# DummyLoad.net
KiCad netlist of a schematic drawn in EAGLE
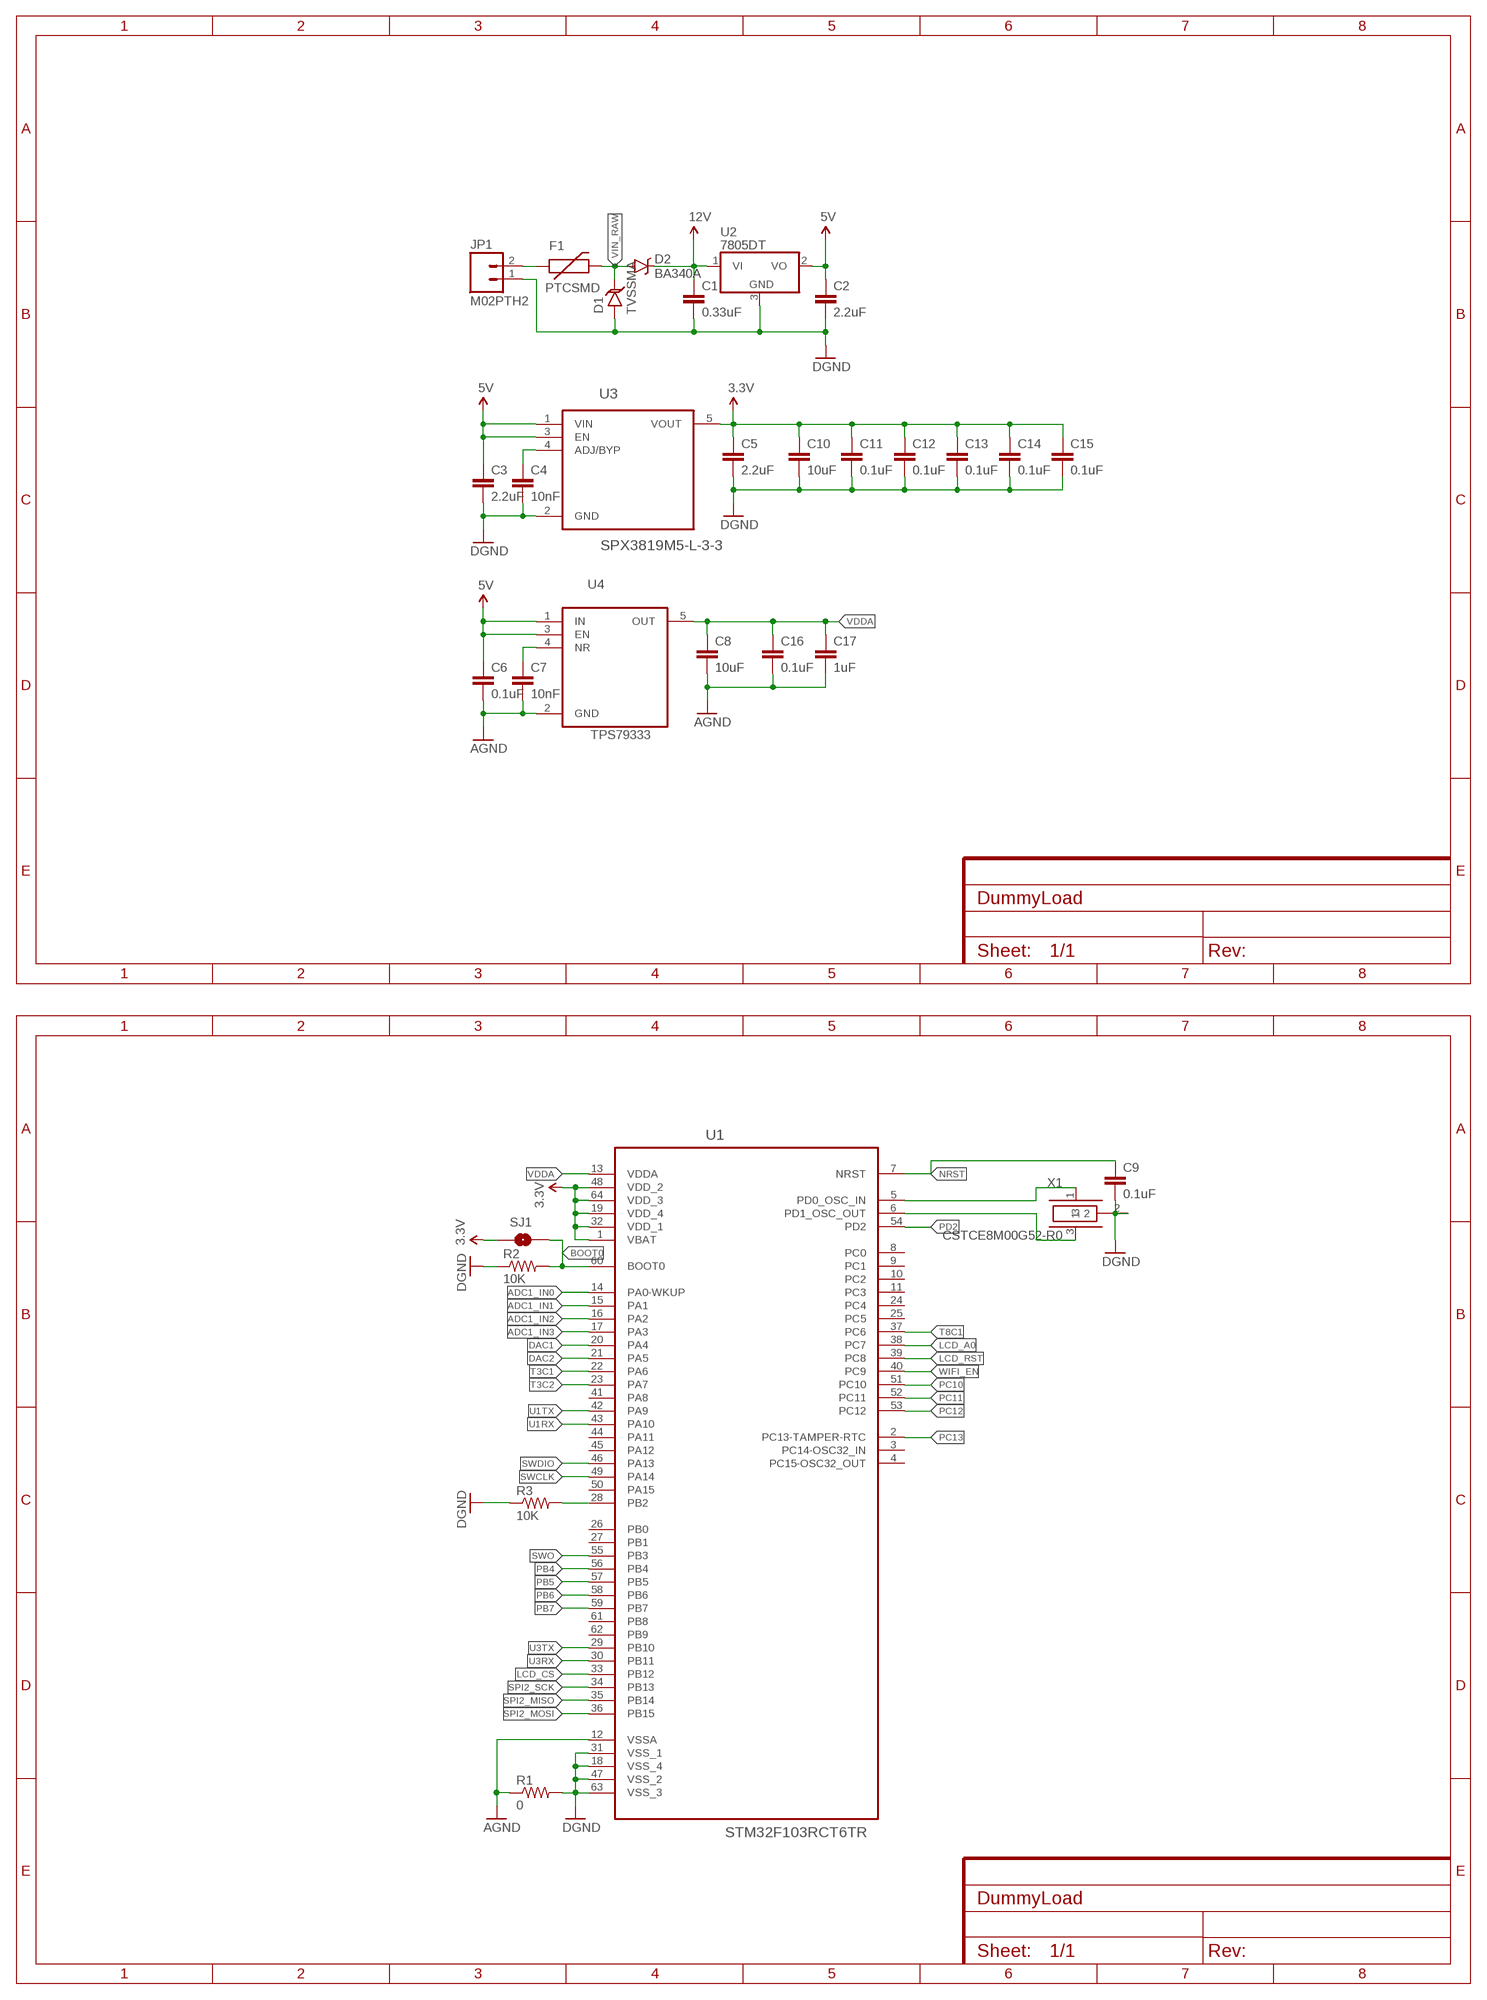
[diagram p0: schematic, sheet 1, part 1 of 2]
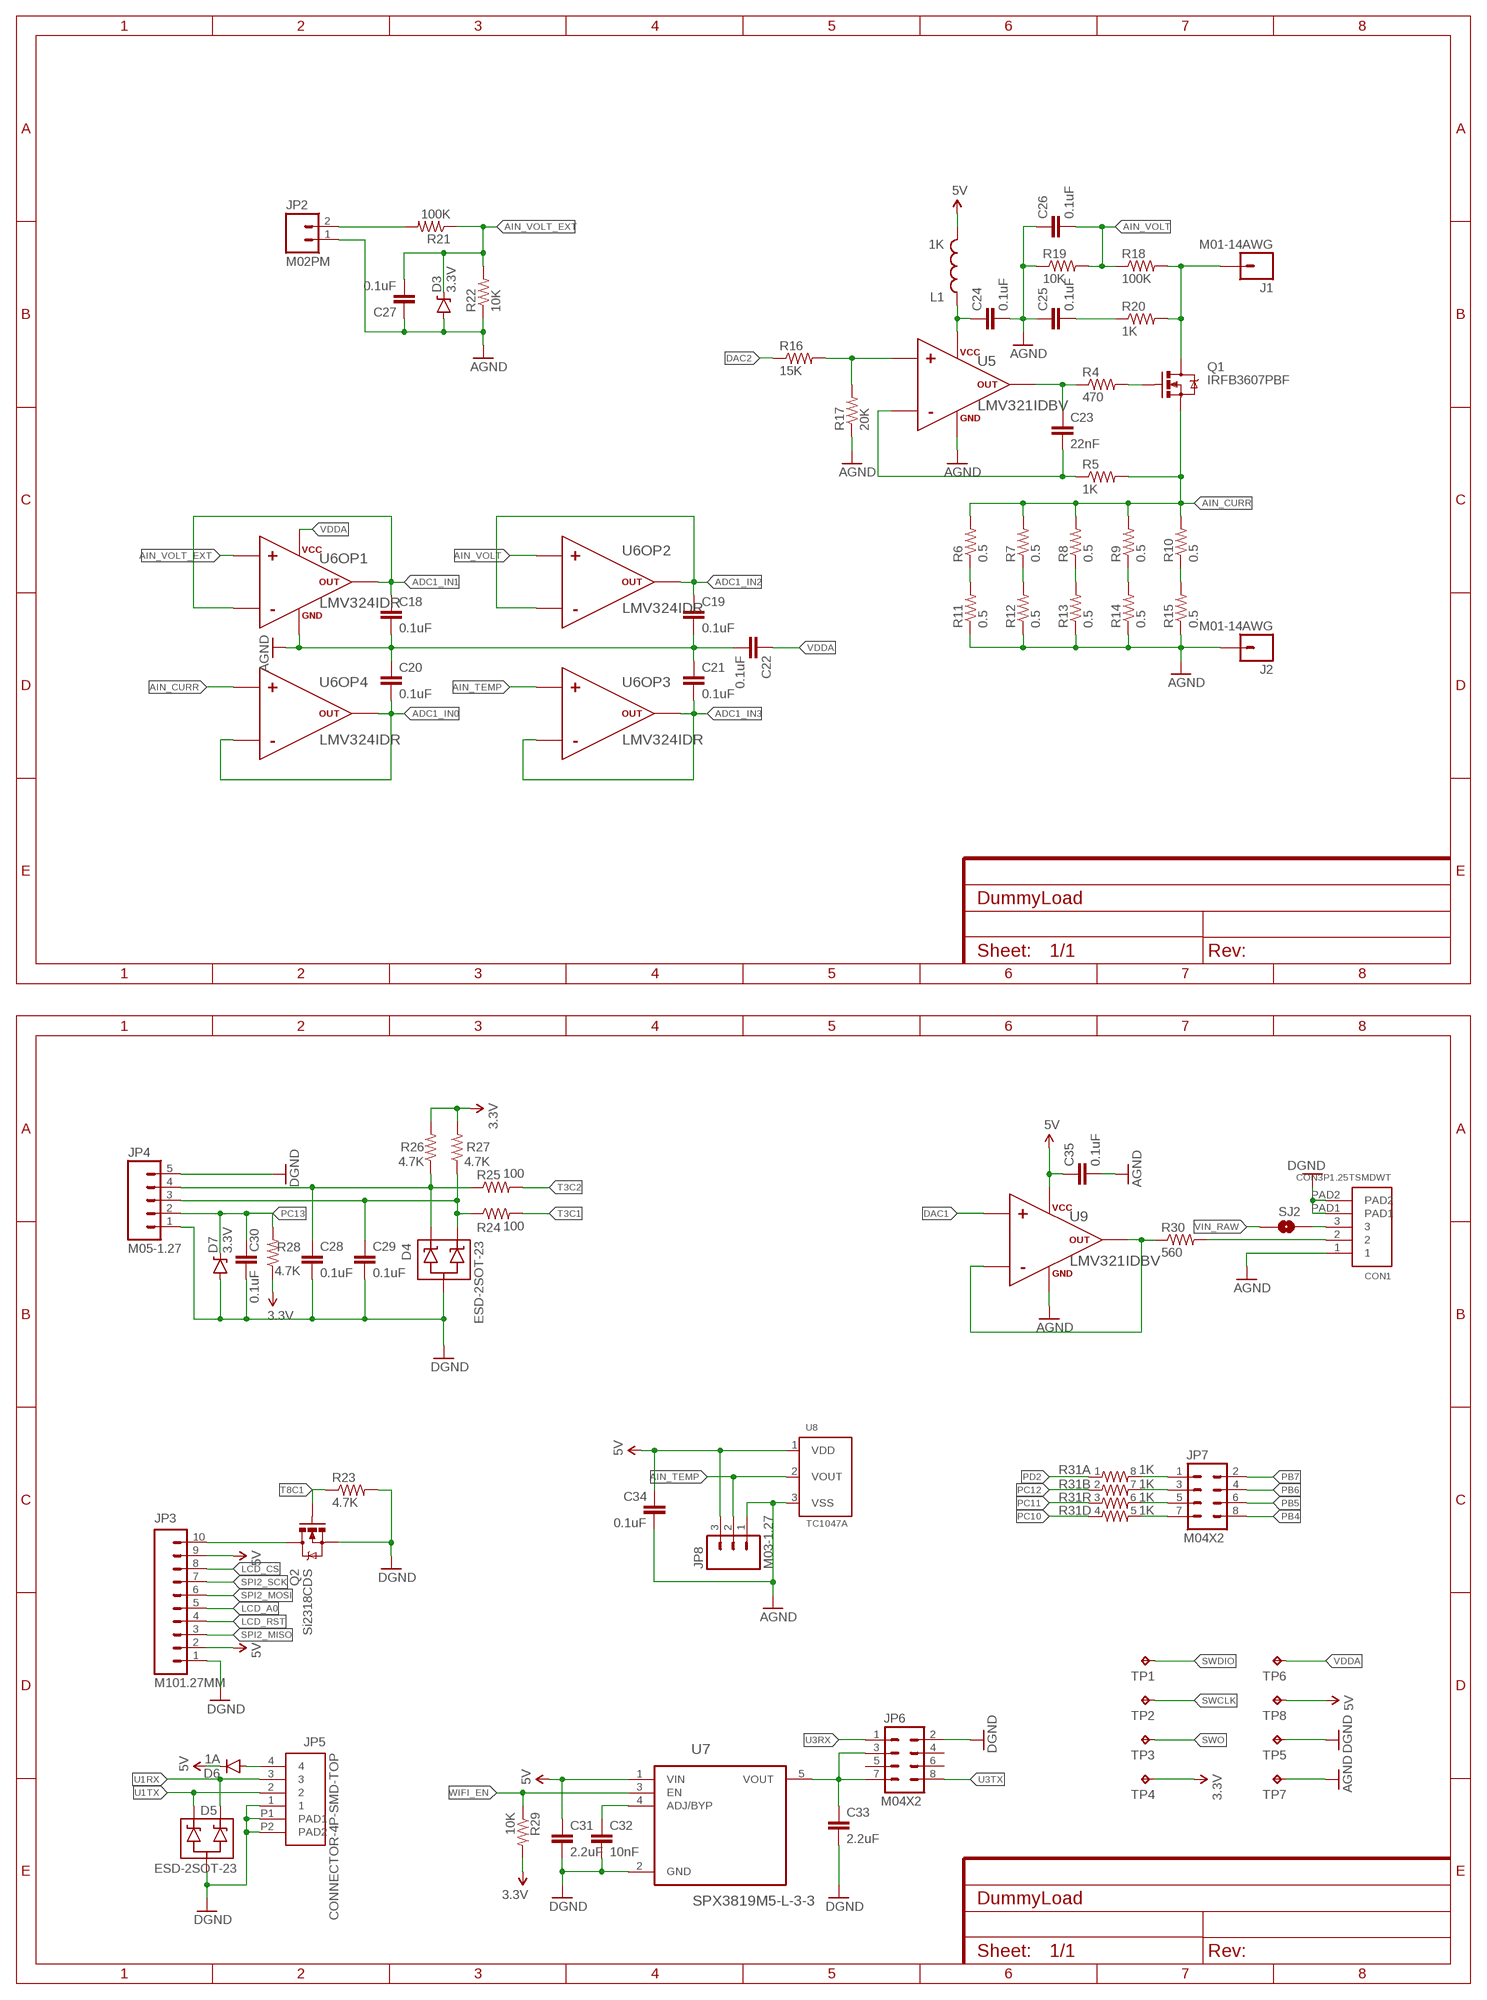
[diagram p1: schematic, sheet 1, part 2 of 2]

(export (version "E")
  (design (tool "Eeschema 10.0.6"))
  (components
    (comp (ref "C1")
      (value "0.33uF")
      (footprint "eagle-import:0603-CAP")
      (libsource (lib "eagle-import") (part "CAP0603-CAP"))
    )
    (comp (ref "C2")
      (value "2.2uF")
      (footprint "eagle-import:0603-CAP")
      (libsource (lib "eagle-import") (part "CAP0603-CAP"))
    )
    (comp (ref "C3")
      (value "2.2uF")
      (footprint "eagle-import:0603-CAP")
      (libsource (lib "eagle-import") (part "CAP0603-CAP"))
    )
    (comp (ref "C4")
      (value "10nF")
      (footprint "eagle-import:0603-CAP")
      (libsource (lib "eagle-import") (part "CAP0603-CAP"))
    )
    (comp (ref "C5")
      (value "2.2uF")
      (footprint "eagle-import:0603-CAP")
      (libsource (lib "eagle-import") (part "CAP0603-CAP"))
    )
    (comp (ref "C6")
      (value "0.1uF")
      (footprint "eagle-import:0603-CAP")
      (libsource (lib "eagle-import") (part "CAP0603-CAP"))
    )
    (comp (ref "C7")
      (value "10nF")
      (footprint "eagle-import:0603-CAP")
      (libsource (lib "eagle-import") (part "CAP0603-CAP"))
    )
    (comp (ref "C8")
      (value "10uF")
      (footprint "eagle-import:0603-CAP")
      (libsource (lib "eagle-import") (part "CAP0603-CAP"))
    )
    (comp (ref "C9")
      (value "0.1uF")
      (footprint "eagle-import:0603-CAP")
      (libsource (lib "eagle-import") (part "CAP0603-CAP"))
    )
    (comp (ref "C10")
      (value "10uF")
      (footprint "eagle-import:0603-CAP")
      (libsource (lib "eagle-import") (part "CAP0603-CAP"))
    )
    (comp (ref "C11")
      (value "0.1uF")
      (footprint "eagle-import:0603-CAP")
      (libsource (lib "eagle-import") (part "CAP0603-CAP"))
    )
    (comp (ref "C12")
      (value "0.1uF")
      (footprint "eagle-import:0603-CAP")
      (libsource (lib "eagle-import") (part "CAP0603-CAP"))
    )
    (comp (ref "C13")
      (value "0.1uF")
      (footprint "eagle-import:0603-CAP")
      (libsource (lib "eagle-import") (part "CAP0603-CAP"))
    )
    (comp (ref "C14")
      (value "0.1uF")
      (footprint "eagle-import:0603-CAP")
      (libsource (lib "eagle-import") (part "CAP0603-CAP"))
    )
    (comp (ref "C15")
      (value "0.1uF")
      (footprint "eagle-import:0603-CAP")
      (libsource (lib "eagle-import") (part "CAP0603-CAP"))
    )
    (comp (ref "C16")
      (value "0.1uF")
      (footprint "eagle-import:0603-CAP")
      (libsource (lib "eagle-import") (part "CAP0603-CAP"))
    )
    (comp (ref "C17")
      (value "1uF")
      (footprint "eagle-import:0603-CAP")
      (libsource (lib "eagle-import") (part "CAP0603-CAP"))
    )
    (comp (ref "C18")
      (value "0.1uF")
      (footprint "eagle-import:0603-CAP")
      (libsource (lib "eagle-import") (part "CAP0603-CAP"))
    )
    (comp (ref "C19")
      (value "0.1uF")
      (footprint "eagle-import:0603-CAP")
      (libsource (lib "eagle-import") (part "CAP0603-CAP"))
    )
    (comp (ref "C20")
      (value "0.1uF")
      (footprint "eagle-import:0603-CAP")
      (libsource (lib "eagle-import") (part "CAP0603-CAP"))
    )
    (comp (ref "C21")
      (value "0.1uF")
      (footprint "eagle-import:0603-CAP")
      (libsource (lib "eagle-import") (part "CAP0603-CAP"))
    )
    (comp (ref "C22")
      (value "0.1uF")
      (footprint "eagle-import:0603-CAP")
      (libsource (lib "eagle-import") (part "CAP0603-CAP"))
    )
    (comp (ref "C23")
      (value "22nF")
      (footprint "eagle-import:0603-CAP")
      (libsource (lib "eagle-import") (part "CAP0603-CAP"))
    )
    (comp (ref "C24")
      (value "0.1uF")
      (footprint "eagle-import:0603-CAP")
      (libsource (lib "eagle-import") (part "CAP0603-CAP"))
    )
    (comp (ref "C25")
      (value "0.1uF")
      (footprint "eagle-import:0603-CAP")
      (libsource (lib "eagle-import") (part "0.1UF-25V-5%(0603)"))
    )
    (comp (ref "C26")
      (value "0.1uF")
      (footprint "eagle-import:0603-CAP")
      (libsource (lib "eagle-import") (part "0.1UF-25V-5%(0603)"))
    )
    (comp (ref "C27")
      (value "0.1uF")
      (footprint "eagle-import:0603-CAP")
      (libsource (lib "eagle-import") (part "0.1UF-25V-5%(0603)"))
    )
    (comp (ref "C28")
      (value "0.1uF")
      (footprint "eagle-import:0603-CAP")
      (libsource (lib "eagle-import") (part "CAP0603-CAP"))
    )
    (comp (ref "C29")
      (value "0.1uF")
      (footprint "eagle-import:0603-CAP")
      (libsource (lib "eagle-import") (part "CAP0603-CAP"))
    )
    (comp (ref "C30")
      (value "0.1uF")
      (footprint "eagle-import:0603-CAP")
      (libsource (lib "eagle-import") (part "CAP0603-CAP"))
    )
    (comp (ref "C31")
      (value "2.2uF")
      (footprint "eagle-import:0603-CAP")
      (libsource (lib "eagle-import") (part "CAP0603-CAP"))
    )
    (comp (ref "C32")
      (value "10nF")
      (footprint "eagle-import:0603-CAP")
      (libsource (lib "eagle-import") (part "CAP0603-CAP"))
    )
    (comp (ref "C33")
      (value "2.2uF")
      (footprint "eagle-import:0603-CAP")
      (libsource (lib "eagle-import") (part "CAP0603-CAP"))
    )
    (comp (ref "C34")
      (value "0.1uF")
      (footprint "eagle-import:0603-CAP")
      (libsource (lib "eagle-import") (part "CAP0603-CAP"))
    )
    (comp (ref "C35")
      (value "0.1uF")
      (footprint "eagle-import:0603-CAP")
      (libsource (lib "eagle-import") (part "CAP0603-CAP"))
    )
    (comp (ref "CON1")
      (value "CON3P1.25TSMDWT")
      (footprint "eagle-import:1.25T3P")
      (libsource (lib "eagle-import") (part "CON3P1.25TSMDWT"))
    )
    (comp (ref "D1")
      (value "TVSSMA")
      (footprint "eagle-import:SMA-DIODE")
      (libsource (lib "eagle-import") (part "TVSSMA"))
    )
    (comp (ref "D2")
      (value "BA340A")
      (footprint "eagle-import:SMA-DIODE")
      (libsource (lib "eagle-import") (part "B340A"))
    )
    (comp (ref "D3")
      (value "3.3V")
      (footprint "eagle-import:SOD-323")
      (libsource (lib "eagle-import") (part "DIODE-ZENER3.3V"))
    )
    (comp (ref "D4")
      (value "ESD-2SOT-23")
      (footprint "eagle-import:SOT23-3")
      (libsource (lib "eagle-import") (part "ESD-2SOT-23"))
    )
    (comp (ref "D5")
      (value "ESD-2SOT-23")
      (footprint "eagle-import:SOT23-3")
      (libsource (lib "eagle-import") (part "ESD-2SOT-23"))
    )
    (comp (ref "D6")
      (value "1A")
      (footprint "eagle-import:SOD-123")
      (libsource (lib "eagle-import") (part "DIODESOD123"))
    )
    (comp (ref "D7")
      (value "3.3V")
      (footprint "eagle-import:SOD-323")
      (libsource (lib "eagle-import") (part "DIODE-ZENER3.3V"))
    )
    (comp (ref "F1")
      (value "PTCSMD")
      (footprint "eagle-import:PTC-1206")
      (libsource (lib "eagle-import") (part "PTCSMD"))
    )
    (comp (ref "J1")
      (value "M01-14AWG")
      (footprint "eagle-import:PTH1.8MM")
      (libsource (lib "eagle-import") (part "M01-14AWG"))
    )
    (comp (ref "J2")
      (value "M01-14AWG")
      (footprint "eagle-import:PTH1.8MM")
      (libsource (lib "eagle-import") (part "M01-14AWG"))
    )
    (comp (ref "JP1")
      (value "M02PTH2")
      (footprint "eagle-import:1X02_BIG")
      (libsource (lib "eagle-import") (part "M02PTH2"))
    )
    (comp (ref "JP2")
      (value "M02PM")
      (footprint "eagle-import:1X02_PM")
      (libsource (lib "eagle-import") (part "M02PM"))
    )
    (comp (ref "JP3")
      (value "M101.27MM")
      (footprint "eagle-import:1X10-1.27MM")
      (libsource (lib "eagle-import") (part "M101.27MM"))
    )
    (comp (ref "JP4")
      (value "M05-1.27")
      (footprint "eagle-import:1X05-1.27MM")
      (libsource (lib "eagle-import") (part "M051.27MM"))
    )
    (comp (ref "JP5")
      (value "CONNECTOR-4P-SMD-TOP")
      (footprint "eagle-import:PH2-4T")
      (libsource (lib "eagle-import") (part "CONNECTOR-4P-SMD-TOP"))
    )
    (comp (ref "JP6")
      (value "M04X2")
      (footprint "eagle-import:2X4")
      (libsource (lib "eagle-import") (part "M04X2"))
    )
    (comp (ref "JP7")
      (value "M04X2")
      (footprint "eagle-import:2X4")
      (libsource (lib "eagle-import") (part "M04X2"))
    )
    (comp (ref "JP8")
      (value "M03-1.27")
      (footprint "eagle-import:1X03-1.27MM")
      (libsource (lib "eagle-import") (part "M03M03-1.27MM"))
    )
    (comp (ref "L1")
      (value "1K")
      (footprint "eagle-import:0603")
      (libsource (lib "eagle-import") (part "INDUCTOR0603"))
    )
    (comp (ref "Q1")
      (value "IRFB3607PBF")
      (footprint "eagle-import:TO220V")
      (libsource (lib "eagle-import") (part "MOSFET-NCHANNELFQP30N06L"))
    )
    (comp (ref "Q2")
      (value "Si2318CDS")
      (footprint "eagle-import:SOT23-3")
      (libsource (lib "eagle-import") (part "MOSFET-NCHANNELBSS123LT1G"))
    )
    (comp (ref "R1")
      (value "0")
      (footprint "eagle-import:0603")
      (libsource (lib "eagle-import") (part "0OHM-1/10W-5%(0603)"))
    )
    (comp (ref "R2")
      (value "10K")
      (footprint "eagle-import:0603-RES")
      (libsource (lib "eagle-import") (part "SparkFun-Resistors_RESISTOR0603-RES"))
    )
    (comp (ref "R3")
      (value "10K")
      (footprint "eagle-import:0603-RES")
      (libsource (lib "eagle-import") (part "SparkFun-Resistors_RESISTOR0603-RES"))
    )
    (comp (ref "R4")
      (value "470")
      (footprint "eagle-import:0603-RES")
      (libsource (lib "eagle-import") (part "SparkFun-Resistors_RESISTOR0603-RES"))
    )
    (comp (ref "R5")
      (value "1K")
      (footprint "eagle-import:0603-RES")
      (libsource (lib "eagle-import") (part "SparkFun-Resistors_RESISTOR0603-RES"))
    )
    (comp (ref "R6")
      (value "0.5")
      (footprint "eagle-import:R2512")
      (libsource (lib "eagle-import") (part "SparkFun-Resistors_RESISTOR2512"))
    )
    (comp (ref "R7")
      (value "0.5")
      (footprint "eagle-import:R2512")
      (libsource (lib "eagle-import") (part "SparkFun-Resistors_RESISTOR2512"))
    )
    (comp (ref "R8")
      (value "0.5")
      (footprint "eagle-import:R2512")
      (libsource (lib "eagle-import") (part "SparkFun-Resistors_RESISTOR2512"))
    )
    (comp (ref "R9")
      (value "0.5")
      (footprint "eagle-import:R2512")
      (libsource (lib "eagle-import") (part "SparkFun-Resistors_RESISTOR2512"))
    )
    (comp (ref "R10")
      (value "0.5")
      (footprint "eagle-import:R2512")
      (libsource (lib "eagle-import") (part "SparkFun-Resistors_RESISTOR2512"))
    )
    (comp (ref "R11")
      (value "0.5")
      (footprint "eagle-import:R2512")
      (libsource (lib "eagle-import") (part "SparkFun-Resistors_RESISTOR2512"))
    )
    (comp (ref "R12")
      (value "0.5")
      (footprint "eagle-import:R2512")
      (libsource (lib "eagle-import") (part "SparkFun-Resistors_RESISTOR2512"))
    )
    (comp (ref "R13")
      (value "0.5")
      (footprint "eagle-import:R2512")
      (libsource (lib "eagle-import") (part "SparkFun-Resistors_RESISTOR2512"))
    )
    (comp (ref "R14")
      (value "0.5")
      (footprint "eagle-import:R2512")
      (libsource (lib "eagle-import") (part "SparkFun-Resistors_RESISTOR2512"))
    )
    (comp (ref "R15")
      (value "0.5")
      (footprint "eagle-import:R2512")
      (libsource (lib "eagle-import") (part "SparkFun-Resistors_RESISTOR2512"))
    )
    (comp (ref "R16")
      (value "15K")
      (footprint "eagle-import:0603-RES")
      (libsource (lib "eagle-import") (part "SparkFun-Resistors_RESISTOR0603-RES"))
    )
    (comp (ref "R17")
      (value "20K")
      (footprint "eagle-import:0603-RES")
      (libsource (lib "eagle-import") (part "SparkFun-Resistors_RESISTOR0603-RES"))
    )
    (comp (ref "R18")
      (value "100K")
      (footprint "eagle-import:0603-RES")
      (libsource (lib "eagle-import") (part "SparkFun-Resistors_RESISTOR0603-RES"))
    )
    (comp (ref "R19")
      (value "10K")
      (footprint "eagle-import:0603-RES")
      (libsource (lib "eagle-import") (part "SparkFun-Resistors_RESISTOR0603-RES"))
    )
    (comp (ref "R20")
      (value "1K")
      (footprint "eagle-import:0603-RES")
      (libsource (lib "eagle-import") (part "SparkFun-Resistors_RESISTOR0603-RES"))
    )
    (comp (ref "R21")
      (value "100K")
      (footprint "eagle-import:0603-RES")
      (libsource (lib "eagle-import") (part "SparkFun-Resistors_RESISTOR0603-RES"))
    )
    (comp (ref "R22")
      (value "10K")
      (footprint "eagle-import:0603-RES")
      (libsource (lib "eagle-import") (part "SparkFun-Resistors_RESISTOR0603-RES"))
    )
    (comp (ref "R23")
      (value "4.7K")
      (footprint "eagle-import:0603-RES")
      (libsource (lib "eagle-import") (part "SparkFun-Resistors_RESISTOR0603-RES"))
    )
    (comp (ref "R24")
      (value "100")
      (footprint "eagle-import:0603-RES")
      (libsource (lib "eagle-import") (part "SparkFun-Resistors_RESISTOR0603-RES"))
    )
    (comp (ref "R25")
      (value "100")
      (footprint "eagle-import:0603-RES")
      (libsource (lib "eagle-import") (part "SparkFun-Resistors_RESISTOR0603-RES"))
    )
    (comp (ref "R26")
      (value "4.7K")
      (footprint "eagle-import:0603-RES")
      (libsource (lib "eagle-import") (part "SparkFun-Resistors_RESISTOR0603-RES"))
    )
    (comp (ref "R27")
      (value "4.7K")
      (footprint "eagle-import:0603-RES")
      (libsource (lib "eagle-import") (part "SparkFun-Resistors_RESISTOR0603-RES"))
    )
    (comp (ref "R28")
      (value "4.7K")
      (footprint "eagle-import:0603-RES")
      (libsource (lib "eagle-import") (part "SparkFun-Resistors_RESISTOR0603-RES"))
    )
    (comp (ref "R29")
      (value "10K")
      (footprint "eagle-import:0603-RES")
      (libsource (lib "eagle-import") (part "10KOHM-1/10W-1%(0603)0603"))
    )
    (comp (ref "R30")
      (value "560")
      (footprint "eagle-import:0603-RES")
      (libsource (lib "eagle-import") (part "RESISTOR0603-RES"))
    )
    (comp (ref "R31")
      (value "1K")
      (footprint "eagle-import:0603-ARV")
      (libsource (lib "eagle-import") (part "RESISTOR-ARRAY0603-ARV"))
    )
    (comp (ref "SJ1")
      (value "JUMPER-PAD-2-NOYES_SILK")
      (footprint "eagle-import:PAD-JUMPER-2-NO_YES_SILK")
      (libsource (lib "eagle-import") (part "JUMPER-PAD-2-NOYES_SILK"))
    )
    (comp (ref "SJ2")
      (value "JUMPER-PAD-2-NO")
      (footprint "eagle-import:PAD-JUMPER-2-NO_NO_SILK")
      (libsource (lib "eagle-import") (part "JUMPER-PAD-2-NO"))
    )
    (comp (ref "TP1")
      (value "TPB1,27")
      (footprint "eagle-import:B1,27")
      (libsource (lib "eagle-import") (part "TPB1,27"))
    )
    (comp (ref "TP2")
      (value "TPB1,27")
      (footprint "eagle-import:B1,27")
      (libsource (lib "eagle-import") (part "TPB1,27"))
    )
    (comp (ref "TP3")
      (value "TPB1,27")
      (footprint "eagle-import:B1,27")
      (libsource (lib "eagle-import") (part "TPB1,27"))
    )
    (comp (ref "TP4")
      (value "TPB1,27")
      (footprint "eagle-import:B1,27")
      (libsource (lib "eagle-import") (part "TPB1,27"))
    )
    (comp (ref "TP5")
      (value "TPB1,27")
      (footprint "eagle-import:B1,27")
      (libsource (lib "eagle-import") (part "TPB1,27"))
    )
    (comp (ref "TP6")
      (value "TPB1,27")
      (footprint "eagle-import:B1,27")
      (libsource (lib "eagle-import") (part "TPB1,27"))
    )
    (comp (ref "TP7")
      (value "TPB1,27")
      (footprint "eagle-import:B1,27")
      (libsource (lib "eagle-import") (part "TPB1,27"))
    )
    (comp (ref "TP8")
      (value "TPB1,27")
      (footprint "eagle-import:B1,27")
      (libsource (lib "eagle-import") (part "TPB1,27"))
    )
    (comp (ref "U1")
      (value "STM32F103RCT6TR")
      (footprint "eagle-import:QFP50P1200X1200X160-64N")
      (fields (field (name "MPN") "STM32F103RCT6"))
      (libsource (lib "eagle-import") (part "STM32F103RCT6TR"))
    )
    (comp (ref "U2")
      (value "7805DT")
      (footprint "eagle-import:TO252")
      (libsource (lib "eagle-import") (part "78DT05"))
    )
    (comp (ref "U3")
      (value "SPX3819M5-L-3-3")
      (footprint "eagle-import:SOT95P280X145-5N")
      (libsource (lib "eagle-import") (part "SPX3819M5-L-3-3"))
    )
    (comp (ref "U4")
      (value "TPS79333")
      (footprint "eagle-import:SOT95P280X145-5N")
      (fields (field (name "MPN") "TPS79333DBVR"))
      (libsource (lib "eagle-import") (part "TPS79333"))
    )
    (comp (ref "U5")
      (value "LMV321IDBV")
      (footprint "eagle-import:SOT23-5")
      (fields (field (name "MPN") "LMV321IDBVR"))
      (libsource (lib "eagle-import") (part "LMV321IDBV"))
    )
    (comp (ref "U6")
      (value "LMV324IDR")
      (footprint "eagle-import:SOIC14")
      (libsource (lib "eagle-import") (part "LMV324IDR"))
    )
    (comp (ref "U7")
      (value "SPX3819M5-L-3-3")
      (footprint "eagle-import:SOT95P280X145-5N")
      (libsource (lib "eagle-import") (part "SPX3819M5-L-3-3"))
    )
    (comp (ref "U8")
      (value "TC1047A")
      (footprint "eagle-import:SOT23")
      (libsource (lib "eagle-import") (part "TC1047A"))
    )
    (comp (ref "U9")
      (value "LMV321IDBV")
      (footprint "eagle-import:SOT23-5")
      (fields (field (name "MPN") "LMV321IDBVR"))
      (libsource (lib "eagle-import") (part "LMV321IDBV"))
    )
    (comp (ref "X1")
      (value "CSTCE8M00G52-R0")
      (footprint "eagle-import:CSTCE_M_G")
      (libsource (lib "eagle-import") (part "CSTCE8M00G52-R0"))
    )
  )
  (nets
    (net (code "1") (name "3.3V") (class "Default")
      (node (ref "C10") (pin "1") (pinfunction "1_1") (pintype "passive"))
      (node (ref "C11") (pin "1") (pinfunction "1_1") (pintype "passive"))
      (node (ref "C12") (pin "1") (pinfunction "1_1") (pintype "passive"))
      (node (ref "C13") (pin "1") (pinfunction "1_1") (pintype "passive"))
      (node (ref "C14") (pin "1") (pinfunction "1_1") (pintype "passive"))
      (node (ref "C15") (pin "1") (pinfunction "1_1") (pintype "passive"))
      (node (ref "C5") (pin "1") (pinfunction "1_1") (pintype "passive"))
      (node (ref "R26") (pin "2") (pinfunction "2_2") (pintype "passive"))
      (node (ref "R27") (pin "2") (pinfunction "2_2") (pintype "passive"))
      (node (ref "R28") (pin "1") (pinfunction "1_1") (pintype "passive"))
      (node (ref "R29") (pin "2") (pinfunction "2_2") (pintype "passive"))
      (node (ref "SJ1") (pin "1") (pinfunction "1_1") (pintype "passive"))
      (node (ref "TP4") (pin "TP") (pinfunction "TP_TP") (pintype "input"))
      (node (ref "U1") (pin "1") (pinfunction "VBAT_1") (pintype "input"))
      (node (ref "U1") (pin "19") (pinfunction "VDD_4_19") (pintype "power_in"))
      (node (ref "U1") (pin "32") (pinfunction "VDD_1_32") (pintype "power_in"))
      (node (ref "U1") (pin "48") (pinfunction "VDD_2_48") (pintype "power_in"))
      (node (ref "U1") (pin "64") (pinfunction "VDD_3_64") (pintype "power_in"))
      (node (ref "U3") (pin "5") (pinfunction "VOUT_5") (pintype "output"))
    )
    (net (code "2") (name "5V") (class "Default")
      (node (ref "C2") (pin "1") (pinfunction "1_1") (pintype "passive"))
      (node (ref "C3") (pin "1") (pinfunction "1_1") (pintype "passive"))
      (node (ref "C31") (pin "1") (pinfunction "1_1") (pintype "passive"))
      (node (ref "C34") (pin "1") (pinfunction "1_1") (pintype "passive"))
      (node (ref "C35") (pin "1") (pinfunction "1_1") (pintype "passive"))
      (node (ref "C6") (pin "1") (pinfunction "1_1") (pintype "passive"))
      (node (ref "D6") (pin "C") (pinfunction "C_C") (pintype "passive"))
      (node (ref "JP3") (pin "2") (pinfunction "2_2") (pintype "passive"))
      (node (ref "JP3") (pin "9") (pinfunction "9_9") (pintype "passive"))
      (node (ref "JP8") (pin "3") (pinfunction "3_3") (pintype "passive"))
      (node (ref "L1") (pin "2") (pinfunction "2_2") (pintype "passive"))
      (node (ref "TP8") (pin "TP") (pinfunction "TP_TP") (pintype "input"))
      (node (ref "U2") (pin "2") (pinfunction "VO_2") (pintype "passive"))
      (node (ref "U3") (pin "1") (pinfunction "VIN_1") (pintype "power_in"))
      (node (ref "U3") (pin "3") (pinfunction "EN_3") (pintype "input"))
      (node (ref "U4") (pin "1") (pinfunction "IN_1") (pintype "input"))
      (node (ref "U4") (pin "3") (pinfunction "EN_3") (pintype "input"))
      (node (ref "U7") (pin "1") (pinfunction "VIN_1") (pintype "power_in"))
      (node (ref "U8") (pin "1") (pinfunction "VDD_1") (pintype "power_in"))
      (node (ref "U9") (pin "5") (pinfunction "VCC+_5") (pintype "power_in"))
    )
    (net (code "3") (name "12V") (class "Default")
      (node (ref "C1") (pin "1") (pinfunction "1_1") (pintype "passive"))
      (node (ref "D2") (pin "C") (pinfunction "C_C") (pintype "passive"))
      (node (ref "U2") (pin "1") (pinfunction "VI_1") (pintype "input"))
    )
    (net (code "4") (name "ADC1_IN0") (class "Default")
      (node (ref "C20") (pin "2") (pinfunction "2_2") (pintype "passive"))
      (node (ref "U1") (pin "14") (pinfunction "PA0-WKUP_14") (pintype "bidirectional"))
      (node (ref "U6") (pin "13") (pinfunction "-_13") (pintype "input"))
      (node (ref "U6") (pin "14") (pinfunction "OUT_14") (pintype "output"))
    )
    (net (code "5") (name "ADC1_IN1") (class "Default")
      (node (ref "C18") (pin "1") (pinfunction "1_1") (pintype "passive"))
      (node (ref "U1") (pin "15") (pinfunction "PA1_15") (pintype "bidirectional"))
      (node (ref "U6") (pin "1") (pinfunction "OUT_1") (pintype "output"))
      (node (ref "U6") (pin "2") (pinfunction "-_2") (pintype "input"))
    )
    (net (code "6") (name "ADC1_IN2") (class "Default")
      (node (ref "C19") (pin "1") (pinfunction "1_1") (pintype "passive"))
      (node (ref "U1") (pin "16") (pinfunction "PA2_16") (pintype "bidirectional"))
      (node (ref "U6") (pin "6") (pinfunction "-_6") (pintype "input"))
      (node (ref "U6") (pin "7") (pinfunction "OUT_7") (pintype "output"))
    )
    (net (code "7") (name "ADC1_IN3") (class "Default")
      (node (ref "C21") (pin "2") (pinfunction "2_2") (pintype "passive"))
      (node (ref "U1") (pin "17") (pinfunction "PA3_17") (pintype "bidirectional"))
      (node (ref "U6") (pin "8") (pinfunction "OUT_8") (pintype "output"))
      (node (ref "U6") (pin "9") (pinfunction "-_9") (pintype "input"))
    )
    (net (code "8") (name "AGND") (class "Default")
      (node (ref "C16") (pin "2") (pinfunction "2_2") (pintype "passive"))
      (node (ref "C17") (pin "2") (pinfunction "2_2") (pintype "passive"))
      (node (ref "C18") (pin "2") (pinfunction "2_2") (pintype "passive"))
      (node (ref "C19") (pin "2") (pinfunction "2_2") (pintype "passive"))
      (node (ref "C20") (pin "1") (pinfunction "1_1") (pintype "passive"))
      (node (ref "C21") (pin "1") (pinfunction "1_1") (pintype "passive"))
      (node (ref "C22") (pin "2") (pinfunction "2_2") (pintype "passive"))
      (node (ref "C24") (pin "2") (pinfunction "2_2") (pintype "passive"))
      (node (ref "C25") (pin "1") (pinfunction "1_1") (pintype "passive"))
      (node (ref "C26") (pin "1") (pinfunction "1_1") (pintype "passive"))
      (node (ref "C27") (pin "1") (pinfunction "1_1") (pintype "passive"))
      (node (ref "C34") (pin "2") (pinfunction "2_2") (pintype "passive"))
      (node (ref "C35") (pin "2") (pinfunction "2_2") (pintype "passive"))
      (node (ref "C6") (pin "2") (pinfunction "2_2") (pintype "passive"))
      (node (ref "C7") (pin "2") (pinfunction "2_2") (pintype "passive"))
      (node (ref "C8") (pin "2") (pinfunction "2_2") (pintype "passive"))
      (node (ref "CON1") (pin "1") (pinfunction "1_1") (pintype "bidirectional"))
      (node (ref "D3") (pin "A") (pinfunction "A_A") (pintype "passive"))
      (node (ref "J2") (pin "1") (pinfunction "1_1") (pintype "passive"))
      (node (ref "JP2") (pin "1") (pinfunction "1_1") (pintype "passive"))
      (node (ref "JP8") (pin "1") (pinfunction "1_1") (pintype "passive"))
      (node (ref "R1") (pin "1") (pinfunction "1_1") (pintype "passive"))
      (node (ref "R11") (pin "1") (pinfunction "1_1") (pintype "passive"))
      (node (ref "R12") (pin "1") (pinfunction "1_1") (pintype "passive"))
      (node (ref "R13") (pin "1") (pinfunction "1_1") (pintype "passive"))
      (node (ref "R14") (pin "1") (pinfunction "1_1") (pintype "passive"))
      (node (ref "R15") (pin "1") (pinfunction "1_1") (pintype "passive"))
      (node (ref "R17") (pin "1") (pinfunction "1_1") (pintype "passive"))
      (node (ref "R19") (pin "1") (pinfunction "1_1") (pintype "passive"))
      (node (ref "R22") (pin "1") (pinfunction "1_1") (pintype "passive"))
      (node (ref "TP7") (pin "TP") (pinfunction "TP_TP") (pintype "input"))
      (node (ref "U1") (pin "12") (pinfunction "VSSA_12") (pintype "passive"))
      (node (ref "U4") (pin "2") (pinfunction "GND_2") (pintype "passive"))
      (node (ref "U5") (pin "2") (pinfunction "GND_2") (pintype "passive"))
      (node (ref "U6") (pin "11") (pinfunction "GND_11") (pintype "passive"))
      (node (ref "U8") (pin "3") (pinfunction "VSS_3") (pintype "passive"))
      (node (ref "U9") (pin "2") (pinfunction "GND_2") (pintype "passive"))
    )
    (net (code "9") (name "AIN_CURR") (class "Default")
      (node (ref "Q1") (pin "3") (pinfunction "S_3") (pintype "passive"))
      (node (ref "R10") (pin "2") (pinfunction "2_2") (pintype "passive"))
      (node (ref "R5") (pin "2") (pinfunction "2_2") (pintype "passive"))
      (node (ref "R6") (pin "2") (pinfunction "2_2") (pintype "passive"))
      (node (ref "R7") (pin "2") (pinfunction "2_2") (pintype "passive"))
      (node (ref "R8") (pin "2") (pinfunction "2_2") (pintype "passive"))
      (node (ref "R9") (pin "2") (pinfunction "2_2") (pintype "passive"))
      (node (ref "U6") (pin "12") (pinfunction "+_12") (pintype "input"))
    )
    (net (code "10") (name "AIN_TEMP") (class "Default")
      (node (ref "JP8") (pin "2") (pinfunction "2_2") (pintype "passive"))
      (node (ref "U6") (pin "10") (pinfunction "+_10") (pintype "input"))
      (node (ref "U8") (pin "2") (pinfunction "VOUT_2") (pintype "output"))
    )
    (net (code "11") (name "AIN_VOLT") (class "Default")
      (node (ref "C26") (pin "2") (pinfunction "2_2") (pintype "passive"))
      (node (ref "R18") (pin "1") (pinfunction "1_1") (pintype "passive"))
      (node (ref "R19") (pin "2") (pinfunction "2_2") (pintype "passive"))
      (node (ref "U6") (pin "5") (pinfunction "+_5") (pintype "input"))
    )
    (net (code "12") (name "AIN_VOLT_EXT") (class "Default")
      (node (ref "C27") (pin "2") (pinfunction "2_2") (pintype "passive"))
      (node (ref "D3") (pin "C") (pinfunction "C_C") (pintype "passive"))
      (node (ref "R21") (pin "1") (pinfunction "1_1") (pintype "passive"))
      (node (ref "R22") (pin "2") (pinfunction "2_2") (pintype "passive"))
      (node (ref "U6") (pin "3") (pinfunction "+_3") (pintype "input"))
    )
    (net (code "13") (name "BOOT0") (class "Default")
      (node (ref "R2") (pin "2") (pinfunction "2_2") (pintype "passive"))
      (node (ref "SJ1") (pin "2") (pinfunction "2_2") (pintype "passive"))
      (node (ref "U1") (pin "60") (pinfunction "BOOT0_60") (pintype "passive"))
    )
    (net (code "14") (name "DAC1") (class "Default")
      (node (ref "U1") (pin "20") (pinfunction "PA4_20") (pintype "bidirectional"))
      (node (ref "U9") (pin "1") (pinfunction "+_1") (pintype "input"))
    )
    (net (code "15") (name "DAC2") (class "Default")
      (node (ref "R16") (pin "1") (pinfunction "1_1") (pintype "passive"))
      (node (ref "U1") (pin "21") (pinfunction "PA5_21") (pintype "bidirectional"))
    )
    (net (code "16") (name "DGND") (class "Default")
      (node (ref "C1") (pin "2") (pinfunction "2_2") (pintype "passive"))
      (node (ref "C10") (pin "2") (pinfunction "2_2") (pintype "passive"))
      (node (ref "C11") (pin "2") (pinfunction "2_2") (pintype "passive"))
      (node (ref "C12") (pin "2") (pinfunction "2_2") (pintype "passive"))
      (node (ref "C13") (pin "2") (pinfunction "2_2") (pintype "passive"))
      (node (ref "C14") (pin "2") (pinfunction "2_2") (pintype "passive"))
      (node (ref "C15") (pin "2") (pinfunction "2_2") (pintype "passive"))
      (node (ref "C2") (pin "2") (pinfunction "2_2") (pintype "passive"))
      (node (ref "C28") (pin "2") (pinfunction "2_2") (pintype "passive"))
      (node (ref "C29") (pin "2") (pinfunction "2_2") (pintype "passive"))
      (node (ref "C3") (pin "2") (pinfunction "2_2") (pintype "passive"))
      (node (ref "C30") (pin "2") (pinfunction "2_2") (pintype "passive"))
      (node (ref "C31") (pin "2") (pinfunction "2_2") (pintype "passive"))
      (node (ref "C32") (pin "2") (pinfunction "2_2") (pintype "passive"))
      (node (ref "C33") (pin "2") (pinfunction "2_2") (pintype "passive"))
      (node (ref "C4") (pin "2") (pinfunction "2_2") (pintype "passive"))
      (node (ref "C5") (pin "2") (pinfunction "2_2") (pintype "passive"))
      (node (ref "C9") (pin "2") (pinfunction "2_2") (pintype "passive"))
      (node (ref "CON1") (pin "PAD1") (pinfunction "PAD1_PAD1") (pintype "bidirectional"))
      (node (ref "CON1") (pin "PAD2") (pinfunction "PAD2_PAD2") (pintype "bidirectional"))
      (node (ref "D1") (pin "A") (pinfunction "A_A") (pintype "passive"))
      (node (ref "D4") (pin "3") (pinfunction "C_3") (pintype "passive"))
      (node (ref "D5") (pin "3") (pinfunction "C_3") (pintype "passive"))
      (node (ref "D7") (pin "A") (pinfunction "A_A") (pintype "passive"))
      (node (ref "JP1") (pin "1") (pinfunction "1_1") (pintype "passive"))
      (node (ref "JP3") (pin "1") (pinfunction "1_1") (pintype "passive"))
      (node (ref "JP4") (pin "1") (pinfunction "1_1") (pintype "passive"))
      (node (ref "JP4") (pin "5") (pinfunction "5_5") (pintype "passive"))
      (node (ref "JP5") (pin "1") (pinfunction "1_1") (pintype "bidirectional"))
      (node (ref "JP5") (pin "P1") (pinfunction "PAD1_P1") (pintype "bidirectional"))
      (node (ref "JP5") (pin "P2") (pinfunction "PAD2_P2") (pintype "bidirectional"))
      (node (ref "JP6") (pin "2") (pinfunction "2_2") (pintype "passive"))
      (node (ref "Q2") (pin "2") (pinfunction "S_2") (pintype "passive"))
      (node (ref "R1") (pin "2") (pinfunction "2_2") (pintype "passive"))
      (node (ref "R2") (pin "1") (pinfunction "1_1") (pintype "passive"))
      (node (ref "R23") (pin "2") (pinfunction "2_2") (pintype "passive"))
      (node (ref "R3") (pin "1") (pinfunction "1_1") (pintype "passive"))
      (node (ref "TP5") (pin "TP") (pinfunction "TP_TP") (pintype "input"))
      (node (ref "U1") (pin "18") (pinfunction "VSS_4_18") (pintype "passive"))
      (node (ref "U1") (pin "31") (pinfunction "VSS_1_31") (pintype "passive"))
      (node (ref "U1") (pin "47") (pinfunction "VSS_2_47") (pintype "passive"))
      (node (ref "U1") (pin "63") (pinfunction "VSS_3_63") (pintype "passive"))
      (node (ref "U2") (pin "3") (pinfunction "GND_3") (pintype "passive"))
      (node (ref "U3") (pin "2") (pinfunction "GND_2") (pintype "passive"))
      (node (ref "U7") (pin "2") (pinfunction "GND_2") (pintype "passive"))
      (node (ref "X1") (pin "2") (pinfunction "2_2") (pintype "bidirectional"))
    )
    (net (code "17") (name "LCD_A0") (class "Default")
      (node (ref "JP3") (pin "5") (pinfunction "5_5") (pintype "passive"))
      (node (ref "U1") (pin "38") (pinfunction "PC7_38") (pintype "bidirectional"))
    )
    (net (code "18") (name "LCD_CS") (class "Default")
      (node (ref "JP3") (pin "8") (pinfunction "8_8") (pintype "passive"))
      (node (ref "U1") (pin "33") (pinfunction "PB12_33") (pintype "bidirectional"))
    )
    (net (code "19") (name "LCD_RST") (class "Default")
      (node (ref "JP3") (pin "4") (pinfunction "4_4") (pintype "passive"))
      (node (ref "U1") (pin "39") (pinfunction "PC8_39") (pintype "bidirectional"))
    )
    (net (code "20") (name "NRST") (class "Default")
      (node (ref "C9") (pin "1") (pinfunction "1_1") (pintype "passive"))
      (node (ref "U1") (pin "7") (pinfunction "NRST_7") (pintype "output"))
    )
    (net (code "21") (name "Net-(C25-Pad2)") (class "Default")
      (node (ref "C25") (pin "2") (pinfunction "2_2") (pintype "passive"))
      (node (ref "R20") (pin "1") (pinfunction "1_1") (pintype "passive"))
    )
    (net (code "22") (name "Net-(CON1-Pad2)") (class "Default")
      (node (ref "CON1") (pin "2") (pinfunction "2_2") (pintype "bidirectional"))
      (node (ref "R30") (pin "2") (pinfunction "2_2") (pintype "passive"))
    )
    (net (code "23") (name "Net-(CON1-Pad3)") (class "Default")
      (node (ref "CON1") (pin "3") (pinfunction "3_3") (pintype "bidirectional"))
      (node (ref "SJ2") (pin "2") (pinfunction "2_2") (pintype "passive"))
    )
    (net (code "24") (name "Net-(D4-A1)") (class "Default")
      (node (ref "C28") (pin "1") (pinfunction "1_1") (pintype "passive"))
      (node (ref "D4") (pin "1") (pinfunction "A1_1") (pintype "passive"))
      (node (ref "JP4") (pin "4") (pinfunction "4_4") (pintype "passive"))
      (node (ref "R25") (pin "1") (pinfunction "1_1") (pintype "passive"))
      (node (ref "R26") (pin "1") (pinfunction "1_1") (pintype "passive"))
    )
    (net (code "25") (name "Net-(D4-A2)") (class "Default")
      (node (ref "C29") (pin "1") (pinfunction "1_1") (pintype "passive"))
      (node (ref "D4") (pin "2") (pinfunction "A2_2") (pintype "passive"))
      (node (ref "JP4") (pin "3") (pinfunction "3_3") (pintype "passive"))
      (node (ref "R24") (pin "1") (pinfunction "1_1") (pintype "passive"))
      (node (ref "R27") (pin "1") (pinfunction "1_1") (pintype "passive"))
    )
    (net (code "26") (name "Net-(D6-PadA)") (class "Default")
      (node (ref "D6") (pin "A") (pinfunction "A_A") (pintype "passive"))
      (node (ref "JP5") (pin "4") (pinfunction "4_4") (pintype "bidirectional"))
    )
    (net (code "27") (name "Net-(F1-Pad1)") (class "Default")
      (node (ref "F1") (pin "1") (pinfunction "1_1") (pintype "bidirectional"))
      (node (ref "JP1") (pin "2") (pinfunction "2_2") (pintype "passive"))
    )
    (net (code "28") (name "Net-(JP2-Pad2)") (class "Default")
      (node (ref "JP2") (pin "2") (pinfunction "2_2") (pintype "passive"))
      (node (ref "R21") (pin "2") (pinfunction "2_2") (pintype "passive"))
    )
    (net (code "29") (name "Net-(Q1-D)") (class "Default")
      (node (ref "J1") (pin "1") (pinfunction "1_1") (pintype "passive"))
      (node (ref "Q1") (pin "2") (pinfunction "D_2") (pintype "passive"))
      (node (ref "R18") (pin "2") (pinfunction "2_2") (pintype "passive"))
      (node (ref "R20") (pin "2") (pinfunction "2_2") (pintype "passive"))
    )
    (net (code "30") (name "Net-(Q1-G)") (class "Default")
      (node (ref "Q1") (pin "1") (pinfunction "G_1") (pintype "passive"))
      (node (ref "R4") (pin "2") (pinfunction "2_2") (pintype "passive"))
    )
    (net (code "31") (name "Net-(Q2-D)") (class "Default")
      (node (ref "JP3") (pin "10") (pinfunction "10_10") (pintype "passive"))
      (node (ref "Q2") (pin "3") (pinfunction "D_3") (pintype "passive"))
    )
    (net (code "32") (name "Net-(R10-Pad1)") (class "Default")
      (node (ref "R10") (pin "1") (pinfunction "1_1") (pintype "passive"))
      (node (ref "R15") (pin "2") (pinfunction "2_2") (pintype "passive"))
    )
    (net (code "33") (name "Net-(R11-Pad2)") (class "Default")
      (node (ref "R11") (pin "2") (pinfunction "2_2") (pintype "passive"))
      (node (ref "R6") (pin "1") (pinfunction "1_1") (pintype "passive"))
    )
    (net (code "34") (name "Net-(R12-Pad2)") (class "Default")
      (node (ref "R12") (pin "2") (pinfunction "2_2") (pintype "passive"))
      (node (ref "R7") (pin "1") (pinfunction "1_1") (pintype "passive"))
    )
    (net (code "35") (name "Net-(R13-Pad2)") (class "Default")
      (node (ref "R13") (pin "2") (pinfunction "2_2") (pintype "passive"))
      (node (ref "R8") (pin "1") (pinfunction "1_1") (pintype "passive"))
    )
    (net (code "36") (name "Net-(R14-Pad2)") (class "Default")
      (node (ref "R14") (pin "2") (pinfunction "2_2") (pintype "passive"))
      (node (ref "R9") (pin "1") (pinfunction "1_1") (pintype "passive"))
    )
    (net (code "37") (name "Net-(R31A-2)") (class "Default")
      (node (ref "JP7") (pin "1") (pinfunction "1_1") (pintype "passive"))
      (node (ref "R31") (pin "8") (pinfunction "2_8") (pintype "passive"))
    )
    (net (code "38") (name "Net-(R31B-2)") (class "Default")
      (node (ref "JP7") (pin "3") (pinfunction "3_3") (pintype "passive"))
      (node (ref "R31") (pin "7") (pinfunction "2_7") (pintype "passive"))
    )
    (net (code "39") (name "Net-(R31C-2)") (class "Default")
      (node (ref "JP7") (pin "7") (pinfunction "7_7") (pintype "passive"))
      (node (ref "R31") (pin "5") (pinfunction "2_5") (pintype "passive"))
    )
    (net (code "40") (name "Net-(R31D-2)") (class "Default")
      (node (ref "JP7") (pin "5") (pinfunction "5_5") (pintype "passive"))
      (node (ref "R31") (pin "6") (pinfunction "2_6") (pintype "passive"))
    )
    (net (code "41") (name "Net-(U1-PB2)") (class "Default")
      (node (ref "R3") (pin "2") (pinfunction "2_2") (pintype "passive"))
      (node (ref "U1") (pin "28") (pinfunction "PB2_28") (pintype "bidirectional"))
    )
    (net (code "42") (name "Net-(U1-PD0_OSC_IN)") (class "Default")
      (node (ref "U1") (pin "5") (pinfunction "PD0_OSC_IN_5") (pintype "input"))
      (node (ref "X1") (pin "1") (pinfunction "1_1") (pintype "bidirectional"))
    )
    (net (code "43") (name "Net-(U1-PD1_OSC_OUT)") (class "Default")
      (node (ref "U1") (pin "6") (pinfunction "PD1_OSC_OUT_6") (pintype "output"))
      (node (ref "X1") (pin "3") (pinfunction "3_3") (pintype "bidirectional"))
    )
    (net (code "44") (name "Net-(U3-ADJ{slash}BYP)") (class "Default")
      (node (ref "C4") (pin "1") (pinfunction "1_1") (pintype "passive"))
      (node (ref "U3") (pin "4") (pinfunction "ADJ/BYP_4") (pintype "passive"))
    )
    (net (code "45") (name "Net-(U4-NR)") (class "Default")
      (node (ref "C7") (pin "1") (pinfunction "1_1") (pintype "passive"))
      (node (ref "U4") (pin "4") (pinfunction "NR_4") (pintype "input"))
    )
    (net (code "46") (name "Net-(U5-+)") (class "Default")
      (node (ref "R16") (pin "2") (pinfunction "2_2") (pintype "passive"))
      (node (ref "R17") (pin "2") (pinfunction "2_2") (pintype "passive"))
      (node (ref "U5") (pin "1") (pinfunction "+_1") (pintype "input"))
    )
    (net (code "47") (name "Net-(U5--)") (class "Default")
      (node (ref "C23") (pin "2") (pinfunction "2_2") (pintype "passive"))
      (node (ref "R5") (pin "1") (pinfunction "1_1") (pintype "passive"))
      (node (ref "U5") (pin "3") (pinfunction "-_3") (pintype "input"))
    )
    (net (code "48") (name "Net-(U5-OUT)") (class "Default")
      (node (ref "C23") (pin "1") (pinfunction "1_1") (pintype "passive"))
      (node (ref "R4") (pin "1") (pinfunction "1_1") (pintype "passive"))
      (node (ref "U5") (pin "4") (pinfunction "OUT_4") (pintype "output"))
    )
    (net (code "49") (name "Net-(U5-VCC+)") (class "Default")
      (node (ref "C24") (pin "1") (pinfunction "1_1") (pintype "passive"))
      (node (ref "L1") (pin "1") (pinfunction "1_1") (pintype "passive"))
      (node (ref "U5") (pin "5") (pinfunction "VCC+_5") (pintype "power_in"))
    )
    (net (code "50") (name "Net-(U7-ADJ{slash}BYP)") (class "Default")
      (node (ref "C32") (pin "1") (pinfunction "1_1") (pintype "passive"))
      (node (ref "U7") (pin "4") (pinfunction "ADJ/BYP_4") (pintype "passive"))
    )
    (net (code "51") (name "Net-(U7-VOUT)") (class "Default")
      (node (ref "C33") (pin "1") (pinfunction "1_1") (pintype "passive"))
      (node (ref "JP6") (pin "3") (pinfunction "3_3") (pintype "passive"))
      (node (ref "JP6") (pin "7") (pinfunction "7_7") (pintype "passive"))
      (node (ref "U7") (pin "5") (pinfunction "VOUT_5") (pintype "output"))
    )
    (net (code "52") (name "Net-(U9--)") (class "Default")
      (node (ref "R30") (pin "1") (pinfunction "1_1") (pintype "passive"))
      (node (ref "U9") (pin "3") (pinfunction "-_3") (pintype "input"))
      (node (ref "U9") (pin "4") (pinfunction "OUT_4") (pintype "output"))
    )
    (net (code "53") (name "PB4") (class "Default")
      (node (ref "JP7") (pin "8") (pinfunction "8_8") (pintype "passive"))
      (node (ref "U1") (pin "56") (pinfunction "PB4_56") (pintype "bidirectional"))
    )
    (net (code "54") (name "PB5") (class "Default")
      (node (ref "JP7") (pin "6") (pinfunction "6_6") (pintype "passive"))
      (node (ref "U1") (pin "57") (pinfunction "PB5_57") (pintype "bidirectional"))
    )
    (net (code "55") (name "PB6") (class "Default")
      (node (ref "JP7") (pin "4") (pinfunction "4_4") (pintype "passive"))
      (node (ref "U1") (pin "58") (pinfunction "PB6_58") (pintype "bidirectional"))
    )
    (net (code "56") (name "PB7") (class "Default")
      (node (ref "JP7") (pin "2") (pinfunction "2_2") (pintype "passive"))
      (node (ref "U1") (pin "59") (pinfunction "PB7_59") (pintype "power_in"))
    )
    (net (code "57") (name "PC10") (class "Default")
      (node (ref "R31") (pin "4") (pinfunction "1_4") (pintype "passive"))
      (node (ref "U1") (pin "51") (pinfunction "PC10_51") (pintype "bidirectional"))
    )
    (net (code "58") (name "PC11") (class "Default")
      (node (ref "R31") (pin "3") (pinfunction "1_3") (pintype "passive"))
      (node (ref "U1") (pin "52") (pinfunction "PC11_52") (pintype "bidirectional"))
    )
    (net (code "59") (name "PC12") (class "Default")
      (node (ref "R31") (pin "2") (pinfunction "1_2") (pintype "passive"))
      (node (ref "U1") (pin "53") (pinfunction "PC12_53") (pintype "bidirectional"))
    )
    (net (code "60") (name "PC13") (class "Default")
      (node (ref "C30") (pin "1") (pinfunction "1_1") (pintype "passive"))
      (node (ref "D7") (pin "C") (pinfunction "C_C") (pintype "passive"))
      (node (ref "JP4") (pin "2") (pinfunction "2_2") (pintype "passive"))
      (node (ref "R28") (pin "2") (pinfunction "2_2") (pintype "passive"))
      (node (ref "U1") (pin "2") (pinfunction "PC13-TAMPER-RTC_2") (pintype "input"))
    )
    (net (code "61") (name "PD2") (class "Default")
      (node (ref "R31") (pin "1") (pinfunction "1_1") (pintype "passive"))
      (node (ref "U1") (pin "54") (pinfunction "PD2_54") (pintype "bidirectional"))
    )
    (net (code "62") (name "SPI2_MISO") (class "Default")
      (node (ref "JP3") (pin "3") (pinfunction "3_3") (pintype "passive"))
      (node (ref "U1") (pin "35") (pinfunction "PB14_35") (pintype "bidirectional"))
    )
    (net (code "63") (name "SPI2_MOSI") (class "Default")
      (node (ref "JP3") (pin "6") (pinfunction "6_6") (pintype "passive"))
      (node (ref "U1") (pin "36") (pinfunction "PB15_36") (pintype "bidirectional"))
    )
    (net (code "64") (name "SPI2_SCK") (class "Default")
      (node (ref "JP3") (pin "7") (pinfunction "7_7") (pintype "passive"))
      (node (ref "U1") (pin "34") (pinfunction "PB13_34") (pintype "bidirectional"))
    )
    (net (code "65") (name "SWCLK") (class "Default")
      (node (ref "TP2") (pin "TP") (pinfunction "TP_TP") (pintype "input"))
      (node (ref "U1") (pin "49") (pinfunction "PA14_49") (pintype "bidirectional"))
    )
    (net (code "66") (name "SWDIO") (class "Default")
      (node (ref "TP1") (pin "TP") (pinfunction "TP_TP") (pintype "input"))
      (node (ref "U1") (pin "46") (pinfunction "PA13_46") (pintype "bidirectional"))
    )
    (net (code "67") (name "SWO") (class "Default")
      (node (ref "TP3") (pin "TP") (pinfunction "TP_TP") (pintype "input"))
      (node (ref "U1") (pin "55") (pinfunction "PB3_55") (pintype "bidirectional"))
    )
    (net (code "68") (name "T3C1") (class "Default")
      (node (ref "R24") (pin "2") (pinfunction "2_2") (pintype "passive"))
      (node (ref "U1") (pin "22") (pinfunction "PA6_22") (pintype "bidirectional"))
    )
    (net (code "69") (name "T3C2") (class "Default")
      (node (ref "R25") (pin "2") (pinfunction "2_2") (pintype "passive"))
      (node (ref "U1") (pin "23") (pinfunction "PA7_23") (pintype "power_in"))
    )
    (net (code "70") (name "T8C1") (class "Default")
      (node (ref "Q2") (pin "1") (pinfunction "G_1") (pintype "passive"))
      (node (ref "R23") (pin "1") (pinfunction "1_1") (pintype "passive"))
      (node (ref "U1") (pin "37") (pinfunction "PC6_37") (pintype "bidirectional"))
    )
    (net (code "71") (name "U1RX") (class "Default")
      (node (ref "D5") (pin "1") (pinfunction "A1_1") (pintype "passive"))
      (node (ref "JP5") (pin "3") (pinfunction "3_3") (pintype "bidirectional"))
      (node (ref "U1") (pin "43") (pinfunction "PA10_43") (pintype "bidirectional"))
    )
    (net (code "72") (name "U1TX") (class "Default")
      (node (ref "D5") (pin "2") (pinfunction "A2_2") (pintype "passive"))
      (node (ref "JP5") (pin "2") (pinfunction "2_2") (pintype "bidirectional"))
      (node (ref "U1") (pin "42") (pinfunction "PA9_42") (pintype "bidirectional"))
    )
    (net (code "73") (name "U3RX") (class "Default")
      (node (ref "JP6") (pin "1") (pinfunction "1_1") (pintype "passive"))
      (node (ref "U1") (pin "30") (pinfunction "PB11_30") (pintype "bidirectional"))
    )
    (net (code "74") (name "U3TX") (class "Default")
      (node (ref "JP6") (pin "8") (pinfunction "8_8") (pintype "passive"))
      (node (ref "U1") (pin "29") (pinfunction "PB10_29") (pintype "bidirectional"))
    )
    (net (code "75") (name "VDDA") (class "Default")
      (node (ref "C16") (pin "1") (pinfunction "1_1") (pintype "passive"))
      (node (ref "C17") (pin "1") (pinfunction "1_1") (pintype "passive"))
      (node (ref "C22") (pin "1") (pinfunction "1_1") (pintype "passive"))
      (node (ref "C8") (pin "1") (pinfunction "1_1") (pintype "passive"))
      (node (ref "TP6") (pin "TP") (pinfunction "TP_TP") (pintype "input"))
      (node (ref "U1") (pin "13") (pinfunction "VDDA_13") (pintype "power_in"))
      (node (ref "U4") (pin "5") (pinfunction "OUT_5") (pintype "output"))
      (node (ref "U6") (pin "4") (pinfunction "VCC+_4") (pintype "power_in"))
    )
    (net (code "76") (name "VIN_RAW") (class "Default")
      (node (ref "D1") (pin "C") (pinfunction "C_C") (pintype "passive"))
      (node (ref "D2") (pin "A") (pinfunction "A_A") (pintype "passive"))
      (node (ref "F1") (pin "2") (pinfunction "2_2") (pintype "bidirectional"))
      (node (ref "SJ2") (pin "1") (pinfunction "1_1") (pintype "passive"))
    )
    (net (code "77") (name "WIFI_EN") (class "Default")
      (node (ref "R29") (pin "1") (pinfunction "1_1") (pintype "passive"))
      (node (ref "U1") (pin "40") (pinfunction "PC9_40") (pintype "bidirectional"))
      (node (ref "U7") (pin "3") (pinfunction "EN_3") (pintype "input"))
    )
    (net (code "78") (name "unconnected-(JP6-Pad4)") (class "Default")
      (node (ref "JP6") (pin "4") (pinfunction "4_4") (pintype "passive"))
    )
    (net (code "79") (name "unconnected-(JP6-Pad5)") (class "Default")
      (node (ref "JP6") (pin "5") (pinfunction "5_5") (pintype "passive"))
    )
    (net (code "80") (name "unconnected-(JP6-Pad6)") (class "Default")
      (node (ref "JP6") (pin "6") (pinfunction "6_6") (pintype "passive"))
    )
    (net (code "81") (name "unconnected-(U1-PA8-Pad41)") (class "Default")
      (node (ref "U1") (pin "41") (pinfunction "PA8_41") (pintype "bidirectional"))
    )
    (net (code "82") (name "unconnected-(U1-PA11-Pad44)") (class "Default")
      (node (ref "U1") (pin "44") (pinfunction "PA11_44") (pintype "bidirectional"))
    )
    (net (code "83") (name "unconnected-(U1-PA12-Pad45)") (class "Default")
      (node (ref "U1") (pin "45") (pinfunction "PA12_45") (pintype "bidirectional"))
    )
    (net (code "84") (name "unconnected-(U1-PA15-Pad50)") (class "Default")
      (node (ref "U1") (pin "50") (pinfunction "PA15_50") (pintype "bidirectional"))
    )
    (net (code "85") (name "unconnected-(U1-PB0-Pad26)") (class "Default")
      (node (ref "U1") (pin "26") (pinfunction "PB0_26") (pintype "bidirectional"))
    )
    (net (code "86") (name "unconnected-(U1-PB1-Pad27)") (class "Default")
      (node (ref "U1") (pin "27") (pinfunction "PB1_27") (pintype "bidirectional"))
    )
    (net (code "87") (name "unconnected-(U1-PB8-Pad61)") (class "Default")
      (node (ref "U1") (pin "61") (pinfunction "PB8_61") (pintype "bidirectional"))
    )
    (net (code "88") (name "unconnected-(U1-PB9-Pad62)") (class "Default")
      (node (ref "U1") (pin "62") (pinfunction "PB9_62") (pintype "bidirectional"))
    )
    (net (code "89") (name "unconnected-(U1-PC0-Pad8)") (class "Default")
      (node (ref "U1") (pin "8") (pinfunction "PC0_8") (pintype "bidirectional"))
    )
    (net (code "90") (name "unconnected-(U1-PC1-Pad9)") (class "Default")
      (node (ref "U1") (pin "9") (pinfunction "PC1_9") (pintype "bidirectional"))
    )
    (net (code "91") (name "unconnected-(U1-PC2-Pad10)") (class "Default")
      (node (ref "U1") (pin "10") (pinfunction "PC2_10") (pintype "bidirectional"))
    )
    (net (code "92") (name "unconnected-(U1-PC3-Pad11)") (class "Default")
      (node (ref "U1") (pin "11") (pinfunction "PC3_11") (pintype "bidirectional"))
    )
    (net (code "93") (name "unconnected-(U1-PC4-Pad24)") (class "Default")
      (node (ref "U1") (pin "24") (pinfunction "PC4_24") (pintype "passive"))
    )
    (net (code "94") (name "unconnected-(U1-PC5-Pad25)") (class "Default")
      (node (ref "U1") (pin "25") (pinfunction "PC5_25") (pintype "bidirectional"))
    )
    (net (code "95") (name "unconnected-(U1-PC14-OSC32_IN-Pad3)") (class "Default")
      (node (ref "U1") (pin "3") (pinfunction "PC14-OSC32_IN_3") (pintype "input"))
    )
    (net (code "96") (name "unconnected-(U1-PC15-OSC32_OUT-Pad4)") (class "Default")
      (node (ref "U1") (pin "4") (pinfunction "PC15-OSC32_OUT_4") (pintype "output"))
    )
  )
)
